# Test.net
KiCad netlist of a schematic drawn in EAGLE
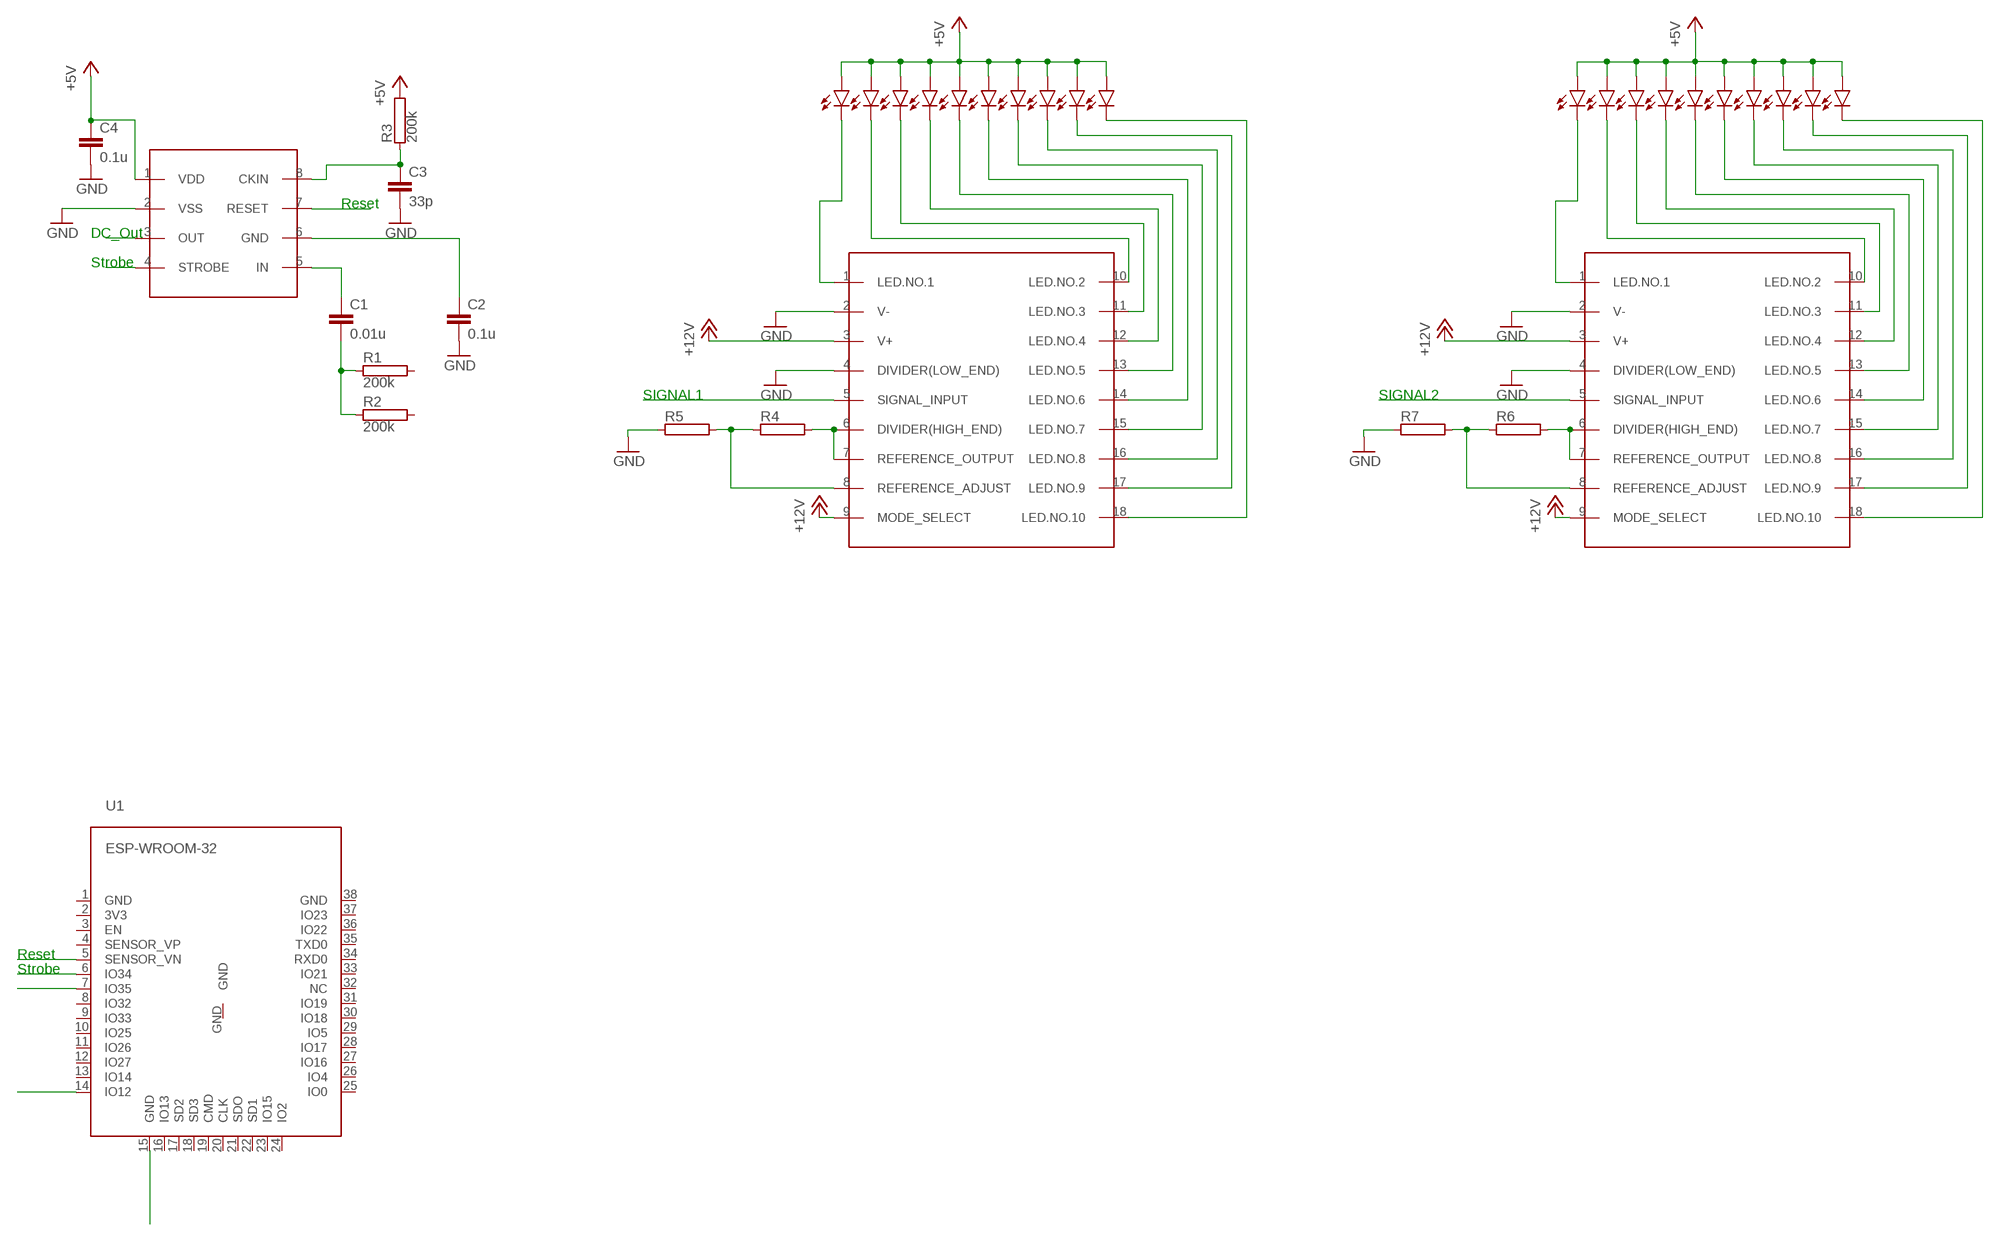
[diagram p0: schematic, sheet 1]

(export (version "E")
  (design (tool "Eeschema 10.0.6"))
  (components
    (comp (ref "C1")
      (value "0.01u")
      (footprint "eagle-import:C2.5-2")
      (libsource (lib "eagle-import") (part "C2.5/2"))
    )
    (comp (ref "C2")
      (value "0.1u")
      (footprint "eagle-import:C2.5-2")
      (libsource (lib "eagle-import") (part "C2.5/2"))
    )
    (comp (ref "C3")
      (value "33p")
      (footprint "eagle-import:C2.5-2")
      (libsource (lib "eagle-import") (part "C2.5/2"))
    )
    (comp (ref "C4")
      (value "0.1u")
      (footprint "eagle-import:C2.5-2")
      (libsource (lib "eagle-import") (part "C2.5/2"))
    )
    (comp (ref "R1")
      (value "200k")
      (footprint "eagle-import:AC01")
      (libsource (lib "eagle-import") (part "RAC01"))
    )
    (comp (ref "R2")
      (value "200k")
      (footprint "eagle-import:AC01")
      (libsource (lib "eagle-import") (part "RAC01"))
    )
    (comp (ref "R3")
      (value "200k")
      (footprint "eagle-import:AC01")
      (libsource (lib "eagle-import") (part "RAC01"))
    )
    (comp (ref "R4")
      (value "RAC01")
      (footprint "eagle-import:AC01")
      (libsource (lib "eagle-import") (part "RAC01"))
    )
    (comp (ref "R5")
      (value "RAC01")
      (footprint "eagle-import:AC01")
      (libsource (lib "eagle-import") (part "RAC01"))
    )
    (comp (ref "R6")
      (value "RAC01")
      (footprint "eagle-import:AC01")
      (libsource (lib "eagle-import") (part "RAC01"))
    )
    (comp (ref "R7")
      (value "RAC01")
      (footprint "eagle-import:AC01")
      (libsource (lib "eagle-import") (part "RAC01"))
    )
    (comp (ref "U$1")
      (value "MSGEQ7")
      (footprint "eagle-import:DIL08")
      (libsource (lib "eagle-import") (part "MSGEQ7"))
    )
    (comp (ref "U$2")
      (value "LB10")
      (footprint "eagle-import:LB10")
      (libsource (lib "eagle-import") (part "LB10"))
    )
    (comp (ref "U$3")
      (value "LM3914")
      (footprint "eagle-import:DIL18")
      (libsource (lib "eagle-import") (part "LM3914"))
    )
    (comp (ref "U$4")
      (value "LB10")
      (footprint "eagle-import:LB10")
      (libsource (lib "eagle-import") (part "LB10"))
    )
    (comp (ref "U$5")
      (value "LM3914")
      (footprint "eagle-import:DIL18")
      (libsource (lib "eagle-import") (part "LM3914"))
    )
    (comp (ref "U1")
      (value "ESP-WROOM-32")
      (footprint "eagle-import:ESP-WROOM-32")
      (libsource (lib "eagle-import") (part "ESP-WROOM-32"))
    )
  )
  (nets
    (net (code "1") (name "+5V") (class "Default")
      (node (ref "C4") (pin "1") (pinfunction "1_1") (pintype "passive"))
      (node (ref "R3") (pin "2") (pinfunction "2_2") (pintype "passive"))
      (node (ref "U$1") (pin "1") (pinfunction "VDD_1") (pintype "bidirectional"))
      (node (ref "U$2") (pin "1") (pinfunction "A_1") (pintype "passive"))
      (node (ref "U$2") (pin "10") (pinfunction "A9_10") (pintype "passive"))
      (node (ref "U$2") (pin "2") (pinfunction "A1_2") (pintype "passive"))
      (node (ref "U$2") (pin "3") (pinfunction "A2_3") (pintype "passive"))
      (node (ref "U$2") (pin "4") (pinfunction "A3_4") (pintype "passive"))
      (node (ref "U$2") (pin "5") (pinfunction "A4_5") (pintype "passive"))
      (node (ref "U$2") (pin "6") (pinfunction "A5_6") (pintype "passive"))
      (node (ref "U$2") (pin "7") (pinfunction "A6_7") (pintype "passive"))
      (node (ref "U$2") (pin "8") (pinfunction "A7_8") (pintype "passive"))
      (node (ref "U$2") (pin "9") (pinfunction "A8_9") (pintype "passive"))
      (node (ref "U$4") (pin "1") (pinfunction "A_1") (pintype "passive"))
      (node (ref "U$4") (pin "10") (pinfunction "A9_10") (pintype "passive"))
      (node (ref "U$4") (pin "2") (pinfunction "A1_2") (pintype "passive"))
      (node (ref "U$4") (pin "3") (pinfunction "A2_3") (pintype "passive"))
      (node (ref "U$4") (pin "4") (pinfunction "A3_4") (pintype "passive"))
      (node (ref "U$4") (pin "5") (pinfunction "A4_5") (pintype "passive"))
      (node (ref "U$4") (pin "6") (pinfunction "A5_6") (pintype "passive"))
      (node (ref "U$4") (pin "7") (pinfunction "A6_7") (pintype "passive"))
      (node (ref "U$4") (pin "8") (pinfunction "A7_8") (pintype "passive"))
      (node (ref "U$4") (pin "9") (pinfunction "A8_9") (pintype "passive"))
    )
    (net (code "2") (name "+12V") (class "Default")
      (node (ref "U$3") (pin "3") (pinfunction "V+_3") (pintype "bidirectional"))
      (node (ref "U$3") (pin "9") (pinfunction "MODE_SELECT_9") (pintype "bidirectional"))
      (node (ref "U$5") (pin "3") (pinfunction "V+_3") (pintype "bidirectional"))
      (node (ref "U$5") (pin "9") (pinfunction "MODE_SELECT_9") (pintype "bidirectional"))
    )
    (net (code "3") (name "GND") (class "Default")
      (node (ref "C2") (pin "2") (pinfunction "2_2") (pintype "passive"))
      (node (ref "C3") (pin "2") (pinfunction "2_2") (pintype "passive"))
      (node (ref "C4") (pin "2") (pinfunction "2_2") (pintype "passive"))
      (node (ref "R5") (pin "1") (pinfunction "1_1") (pintype "passive"))
      (node (ref "R7") (pin "1") (pinfunction "1_1") (pintype "passive"))
      (node (ref "U$1") (pin "2") (pinfunction "VSS_2") (pintype "bidirectional"))
      (node (ref "U$3") (pin "2") (pinfunction "V-_2") (pintype "bidirectional"))
      (node (ref "U$3") (pin "4") (pinfunction "DIVIDER(LOW_END)_4") (pintype "bidirectional"))
      (node (ref "U$5") (pin "2") (pinfunction "V-_2") (pintype "bidirectional"))
      (node (ref "U$5") (pin "4") (pinfunction "DIVIDER(LOW_END)_4") (pintype "bidirectional"))
    )
    (net (code "4") (name "Net-(C1-Pad2)") (class "Default")
      (node (ref "C1") (pin "2") (pinfunction "2_2") (pintype "passive"))
      (node (ref "R1") (pin "1") (pinfunction "1_1") (pintype "passive"))
      (node (ref "R2") (pin "1") (pinfunction "1_1") (pintype "passive"))
    )
    (net (code "5") (name "Net-(U$1-CKIN)") (class "Default")
      (node (ref "C3") (pin "1") (pinfunction "1_1") (pintype "passive"))
      (node (ref "R3") (pin "1") (pinfunction "1_1") (pintype "passive"))
      (node (ref "U$1") (pin "8") (pinfunction "CKIN_8") (pintype "bidirectional"))
    )
    (net (code "6") (name "Net-(U$1-GND)") (class "Default")
      (node (ref "C2") (pin "1") (pinfunction "1_1") (pintype "passive"))
      (node (ref "U$1") (pin "6") (pinfunction "GND_6") (pintype "bidirectional"))
    )
    (net (code "7") (name "Net-(U$1-IN)") (class "Default")
      (node (ref "C1") (pin "1") (pinfunction "1_1") (pintype "passive"))
      (node (ref "U$1") (pin "5") (pinfunction "IN_5") (pintype "bidirectional"))
    )
    (net (code "8") (name "Net-(U$2-C)") (class "Default")
      (node (ref "U$2") (pin "11") (pinfunction "C_11") (pintype "passive"))
      (node (ref "U$3") (pin "1") (pinfunction "LED.NO.1_1") (pintype "bidirectional"))
    )
    (net (code "9") (name "Net-(U$2-C1)") (class "Default")
      (node (ref "U$2") (pin "12") (pinfunction "C1_12") (pintype "passive"))
      (node (ref "U$3") (pin "10") (pinfunction "LED.NO.2_10") (pintype "bidirectional"))
    )
    (net (code "10") (name "Net-(U$2-C2)") (class "Default")
      (node (ref "U$2") (pin "13") (pinfunction "C2_13") (pintype "passive"))
      (node (ref "U$3") (pin "11") (pinfunction "LED.NO.3_11") (pintype "bidirectional"))
    )
    (net (code "11") (name "Net-(U$2-C3)") (class "Default")
      (node (ref "U$2") (pin "14") (pinfunction "C3_14") (pintype "passive"))
      (node (ref "U$3") (pin "12") (pinfunction "LED.NO.4_12") (pintype "bidirectional"))
    )
    (net (code "12") (name "Net-(U$2-C4)") (class "Default")
      (node (ref "U$2") (pin "15") (pinfunction "C4_15") (pintype "passive"))
      (node (ref "U$3") (pin "13") (pinfunction "LED.NO.5_13") (pintype "bidirectional"))
    )
    (net (code "13") (name "Net-(U$2-C5)") (class "Default")
      (node (ref "U$2") (pin "16") (pinfunction "C5_16") (pintype "passive"))
      (node (ref "U$3") (pin "14") (pinfunction "LED.NO.6_14") (pintype "bidirectional"))
    )
    (net (code "14") (name "Net-(U$2-C6)") (class "Default")
      (node (ref "U$2") (pin "17") (pinfunction "C6_17") (pintype "passive"))
      (node (ref "U$3") (pin "15") (pinfunction "LED.NO.7_15") (pintype "bidirectional"))
    )
    (net (code "15") (name "Net-(U$2-C7)") (class "Default")
      (node (ref "U$2") (pin "18") (pinfunction "C7_18") (pintype "passive"))
      (node (ref "U$3") (pin "16") (pinfunction "LED.NO.8_16") (pintype "bidirectional"))
    )
    (net (code "16") (name "Net-(U$2-C8)") (class "Default")
      (node (ref "U$2") (pin "19") (pinfunction "C8_19") (pintype "passive"))
      (node (ref "U$3") (pin "17") (pinfunction "LED.NO.9_17") (pintype "bidirectional"))
    )
    (net (code "17") (name "Net-(U$2-C9)") (class "Default")
      (node (ref "U$2") (pin "20") (pinfunction "C9_20") (pintype "passive"))
      (node (ref "U$3") (pin "18") (pinfunction "LED.NO.10_18") (pintype "bidirectional"))
    )
    (net (code "18") (name "Net-(U$3-DIVIDER(HIGH_END))") (class "Default")
      (node (ref "R4") (pin "2") (pinfunction "2_2") (pintype "passive"))
      (node (ref "U$3") (pin "6") (pinfunction "DIVIDER(HIGH_END)_6") (pintype "bidirectional"))
      (node (ref "U$3") (pin "7") (pinfunction "REFERENCE_OUTPUT_7") (pintype "bidirectional"))
    )
    (net (code "19") (name "Net-(U$3-REFERENCE_ADJUST)") (class "Default")
      (node (ref "R4") (pin "1") (pinfunction "1_1") (pintype "passive"))
      (node (ref "R5") (pin "2") (pinfunction "2_2") (pintype "passive"))
      (node (ref "U$3") (pin "8") (pinfunction "REFERENCE_ADJUST_8") (pintype "bidirectional"))
    )
    (net (code "20") (name "Net-(U$4-C)") (class "Default")
      (node (ref "U$4") (pin "11") (pinfunction "C_11") (pintype "passive"))
      (node (ref "U$5") (pin "1") (pinfunction "LED.NO.1_1") (pintype "bidirectional"))
    )
    (net (code "21") (name "Net-(U$4-C1)") (class "Default")
      (node (ref "U$4") (pin "12") (pinfunction "C1_12") (pintype "passive"))
      (node (ref "U$5") (pin "10") (pinfunction "LED.NO.2_10") (pintype "bidirectional"))
    )
    (net (code "22") (name "Net-(U$4-C2)") (class "Default")
      (node (ref "U$4") (pin "13") (pinfunction "C2_13") (pintype "passive"))
      (node (ref "U$5") (pin "11") (pinfunction "LED.NO.3_11") (pintype "bidirectional"))
    )
    (net (code "23") (name "Net-(U$4-C3)") (class "Default")
      (node (ref "U$4") (pin "14") (pinfunction "C3_14") (pintype "passive"))
      (node (ref "U$5") (pin "12") (pinfunction "LED.NO.4_12") (pintype "bidirectional"))
    )
    (net (code "24") (name "Net-(U$4-C4)") (class "Default")
      (node (ref "U$4") (pin "15") (pinfunction "C4_15") (pintype "passive"))
      (node (ref "U$5") (pin "13") (pinfunction "LED.NO.5_13") (pintype "bidirectional"))
    )
    (net (code "25") (name "Net-(U$4-C5)") (class "Default")
      (node (ref "U$4") (pin "16") (pinfunction "C5_16") (pintype "passive"))
      (node (ref "U$5") (pin "14") (pinfunction "LED.NO.6_14") (pintype "bidirectional"))
    )
    (net (code "26") (name "Net-(U$4-C6)") (class "Default")
      (node (ref "U$4") (pin "17") (pinfunction "C6_17") (pintype "passive"))
      (node (ref "U$5") (pin "15") (pinfunction "LED.NO.7_15") (pintype "bidirectional"))
    )
    (net (code "27") (name "Net-(U$4-C7)") (class "Default")
      (node (ref "U$4") (pin "18") (pinfunction "C7_18") (pintype "passive"))
      (node (ref "U$5") (pin "16") (pinfunction "LED.NO.8_16") (pintype "bidirectional"))
    )
    (net (code "28") (name "Net-(U$4-C8)") (class "Default")
      (node (ref "U$4") (pin "19") (pinfunction "C8_19") (pintype "passive"))
      (node (ref "U$5") (pin "17") (pinfunction "LED.NO.9_17") (pintype "bidirectional"))
    )
    (net (code "29") (name "Net-(U$4-C9)") (class "Default")
      (node (ref "U$4") (pin "20") (pinfunction "C9_20") (pintype "passive"))
      (node (ref "U$5") (pin "18") (pinfunction "LED.NO.10_18") (pintype "bidirectional"))
    )
    (net (code "30") (name "Net-(U$5-DIVIDER(HIGH_END))") (class "Default")
      (node (ref "R6") (pin "2") (pinfunction "2_2") (pintype "passive"))
      (node (ref "U$5") (pin "6") (pinfunction "DIVIDER(HIGH_END)_6") (pintype "bidirectional"))
      (node (ref "U$5") (pin "7") (pinfunction "REFERENCE_OUTPUT_7") (pintype "bidirectional"))
    )
    (net (code "31") (name "Net-(U$5-REFERENCE_ADJUST)") (class "Default")
      (node (ref "R6") (pin "1") (pinfunction "1_1") (pintype "passive"))
      (node (ref "R7") (pin "2") (pinfunction "2_2") (pintype "passive"))
      (node (ref "U$5") (pin "8") (pinfunction "REFERENCE_ADJUST_8") (pintype "bidirectional"))
    )
    (net (code "32") (name "unconnected-(R1-Pad2)") (class "Default")
      (node (ref "R1") (pin "2") (pinfunction "2_2") (pintype "passive"))
    )
    (net (code "33") (name "unconnected-(R2-Pad2)") (class "Default")
      (node (ref "R2") (pin "2") (pinfunction "2_2") (pintype "passive"))
    )
    (net (code "34") (name "unconnected-(U$1-OUT-Pad3)") (class "Default")
      (node (ref "U$1") (pin "3") (pinfunction "OUT_3") (pintype "bidirectional"))
    )
    (net (code "35") (name "unconnected-(U$1-RESET-Pad7)") (class "Default")
      (node (ref "U$1") (pin "7") (pinfunction "RESET_7") (pintype "bidirectional"))
    )
    (net (code "36") (name "unconnected-(U$1-STROBE-Pad4)") (class "Default")
      (node (ref "U$1") (pin "4") (pinfunction "STROBE_4") (pintype "bidirectional"))
    )
    (net (code "37") (name "unconnected-(U$3-SIGNAL_INPUT-Pad5)") (class "Default")
      (node (ref "U$3") (pin "5") (pinfunction "SIGNAL_INPUT_5") (pintype "bidirectional"))
    )
    (net (code "38") (name "unconnected-(U$5-SIGNAL_INPUT-Pad5)") (class "Default")
      (node (ref "U$5") (pin "5") (pinfunction "SIGNAL_INPUT_5") (pintype "bidirectional"))
    )
    (net (code "39") (name "unconnected-(U1-3V3-Pad2)") (class "Default")
      (node (ref "U1") (pin "2") (pinfunction "3V3_2") (pintype "bidirectional"))
    )
    (net (code "40") (name "unconnected-(U1-CLK-Pad20)") (class "Default")
      (node (ref "U1") (pin "20") (pinfunction "CLK_20") (pintype "bidirectional"))
    )
    (net (code "41") (name "unconnected-(U1-CMD-Pad19)") (class "Default")
      (node (ref "U1") (pin "19") (pinfunction "CMD_19") (pintype "bidirectional"))
    )
    (net (code "42") (name "unconnected-(U1-EN-Pad3)") (class "Default")
      (node (ref "U1") (pin "3") (pinfunction "EN_3") (pintype "bidirectional"))
    )
    (net (code "43") (name "unconnected-(U1-GND-Pad1)") (class "Default")
      (node (ref "U1") (pin "1") (pinfunction "GND_1") (pintype "bidirectional"))
    )
    (net (code "44") (name "unconnected-(U1-GND-Pad15)") (class "Default")
      (node (ref "U1") (pin "15") (pinfunction "GND_15") (pintype "bidirectional"))
    )
    (net (code "45") (name "unconnected-(U1-GND-Pad38)") (class "Default")
      (node (ref "U1") (pin "38") (pinfunction "GND_38") (pintype "bidirectional"))
    )
    (net (code "46") (name "unconnected-(U1-IO0-Pad25)") (class "Default")
      (node (ref "U1") (pin "25") (pinfunction "IO0_25") (pintype "bidirectional"))
    )
    (net (code "47") (name "unconnected-(U1-IO2-Pad24)") (class "Default")
      (node (ref "U1") (pin "24") (pinfunction "IO2_24") (pintype "bidirectional"))
    )
    (net (code "48") (name "unconnected-(U1-IO4-Pad26)") (class "Default")
      (node (ref "U1") (pin "26") (pinfunction "IO4_26") (pintype "bidirectional"))
    )
    (net (code "49") (name "unconnected-(U1-IO5-Pad29)") (class "Default")
      (node (ref "U1") (pin "29") (pinfunction "IO5_29") (pintype "bidirectional"))
    )
    (net (code "50") (name "unconnected-(U1-IO12-Pad14)") (class "Default")
      (node (ref "U1") (pin "14") (pinfunction "IO12_14") (pintype "bidirectional"))
    )
    (net (code "51") (name "unconnected-(U1-IO13-Pad16)") (class "Default")
      (node (ref "U1") (pin "16") (pinfunction "IO13_16") (pintype "bidirectional"))
    )
    (net (code "52") (name "unconnected-(U1-IO14-Pad13)") (class "Default")
      (node (ref "U1") (pin "13") (pinfunction "IO14_13") (pintype "bidirectional"))
    )
    (net (code "53") (name "unconnected-(U1-IO15-Pad23)") (class "Default")
      (node (ref "U1") (pin "23") (pinfunction "IO15_23") (pintype "bidirectional"))
    )
    (net (code "54") (name "unconnected-(U1-IO16-Pad27)") (class "Default")
      (node (ref "U1") (pin "27") (pinfunction "IO16_27") (pintype "bidirectional"))
    )
    (net (code "55") (name "unconnected-(U1-IO17-Pad28)") (class "Default")
      (node (ref "U1") (pin "28") (pinfunction "IO17_28") (pintype "bidirectional"))
    )
    (net (code "56") (name "unconnected-(U1-IO18-Pad30)") (class "Default")
      (node (ref "U1") (pin "30") (pinfunction "IO18_30") (pintype "bidirectional"))
    )
    (net (code "57") (name "unconnected-(U1-IO19-Pad31)") (class "Default")
      (node (ref "U1") (pin "31") (pinfunction "IO19_31") (pintype "bidirectional"))
    )
    (net (code "58") (name "unconnected-(U1-IO21-Pad33)") (class "Default")
      (node (ref "U1") (pin "33") (pinfunction "IO21_33") (pintype "bidirectional"))
    )
    (net (code "59") (name "unconnected-(U1-IO22-Pad36)") (class "Default")
      (node (ref "U1") (pin "36") (pinfunction "IO22_36") (pintype "bidirectional"))
    )
    (net (code "60") (name "unconnected-(U1-IO23-Pad37)") (class "Default")
      (node (ref "U1") (pin "37") (pinfunction "IO23_37") (pintype "bidirectional"))
    )
    (net (code "61") (name "unconnected-(U1-IO25-Pad10)") (class "Default")
      (node (ref "U1") (pin "10") (pinfunction "IO25_10") (pintype "bidirectional"))
    )
    (net (code "62") (name "unconnected-(U1-IO26-Pad11)") (class "Default")
      (node (ref "U1") (pin "11") (pinfunction "IO26_11") (pintype "bidirectional"))
    )
    (net (code "63") (name "unconnected-(U1-IO27-Pad12)") (class "Default")
      (node (ref "U1") (pin "12") (pinfunction "IO27_12") (pintype "bidirectional"))
    )
    (net (code "64") (name "unconnected-(U1-IO32-Pad8)") (class "Default")
      (node (ref "U1") (pin "8") (pinfunction "IO32_8") (pintype "bidirectional"))
    )
    (net (code "65") (name "unconnected-(U1-IO33-Pad9)") (class "Default")
      (node (ref "U1") (pin "9") (pinfunction "IO33_9") (pintype "bidirectional"))
    )
    (net (code "66") (name "unconnected-(U1-IO34-Pad6)") (class "Default")
      (node (ref "U1") (pin "6") (pinfunction "IO34_6") (pintype "bidirectional"))
    )
    (net (code "67") (name "unconnected-(U1-IO35-Pad7)") (class "Default")
      (node (ref "U1") (pin "7") (pinfunction "IO35_7") (pintype "bidirectional"))
    )
    (net (code "68") (name "unconnected-(U1-NC-Pad32)") (class "Default")
      (node (ref "U1") (pin "32") (pinfunction "NC_32") (pintype "bidirectional"))
    )
    (net (code "69") (name "unconnected-(U1-PadGND)") (class "Default")
      (node (ref "U1") (pin "GND") (pinfunction "GND_GND") (pintype "bidirectional"))
    )
    (net (code "70") (name "unconnected-(U1-RXD0-Pad34)") (class "Default")
      (node (ref "U1") (pin "34") (pinfunction "RXD0_34") (pintype "bidirectional"))
    )
    (net (code "71") (name "unconnected-(U1-SD1-Pad22)") (class "Default")
      (node (ref "U1") (pin "22") (pinfunction "SD1_22") (pintype "bidirectional"))
    )
    (net (code "72") (name "unconnected-(U1-SD2-Pad17)") (class "Default")
      (node (ref "U1") (pin "17") (pinfunction "SD2_17") (pintype "bidirectional"))
    )
    (net (code "73") (name "unconnected-(U1-SD3-Pad18)") (class "Default")
      (node (ref "U1") (pin "18") (pinfunction "SD3_18") (pintype "bidirectional"))
    )
    (net (code "74") (name "unconnected-(U1-SDO-Pad21)") (class "Default")
      (node (ref "U1") (pin "21") (pinfunction "SDO_21") (pintype "bidirectional"))
    )
    (net (code "75") (name "unconnected-(U1-SENSOR_VN-Pad5)") (class "Default")
      (node (ref "U1") (pin "5") (pinfunction "SENSOR_VN_5") (pintype "bidirectional"))
    )
    (net (code "76") (name "unconnected-(U1-SENSOR_VP-Pad4)") (class "Default")
      (node (ref "U1") (pin "4") (pinfunction "SENSOR_VP_4") (pintype "bidirectional"))
    )
    (net (code "77") (name "unconnected-(U1-TXD0-Pad35)") (class "Default")
      (node (ref "U1") (pin "35") (pinfunction "TXD0_35") (pintype "bidirectional"))
    )
  )
)
